# top_schematic.net
KiCad netlist of a schematic drawn in Altium Designer
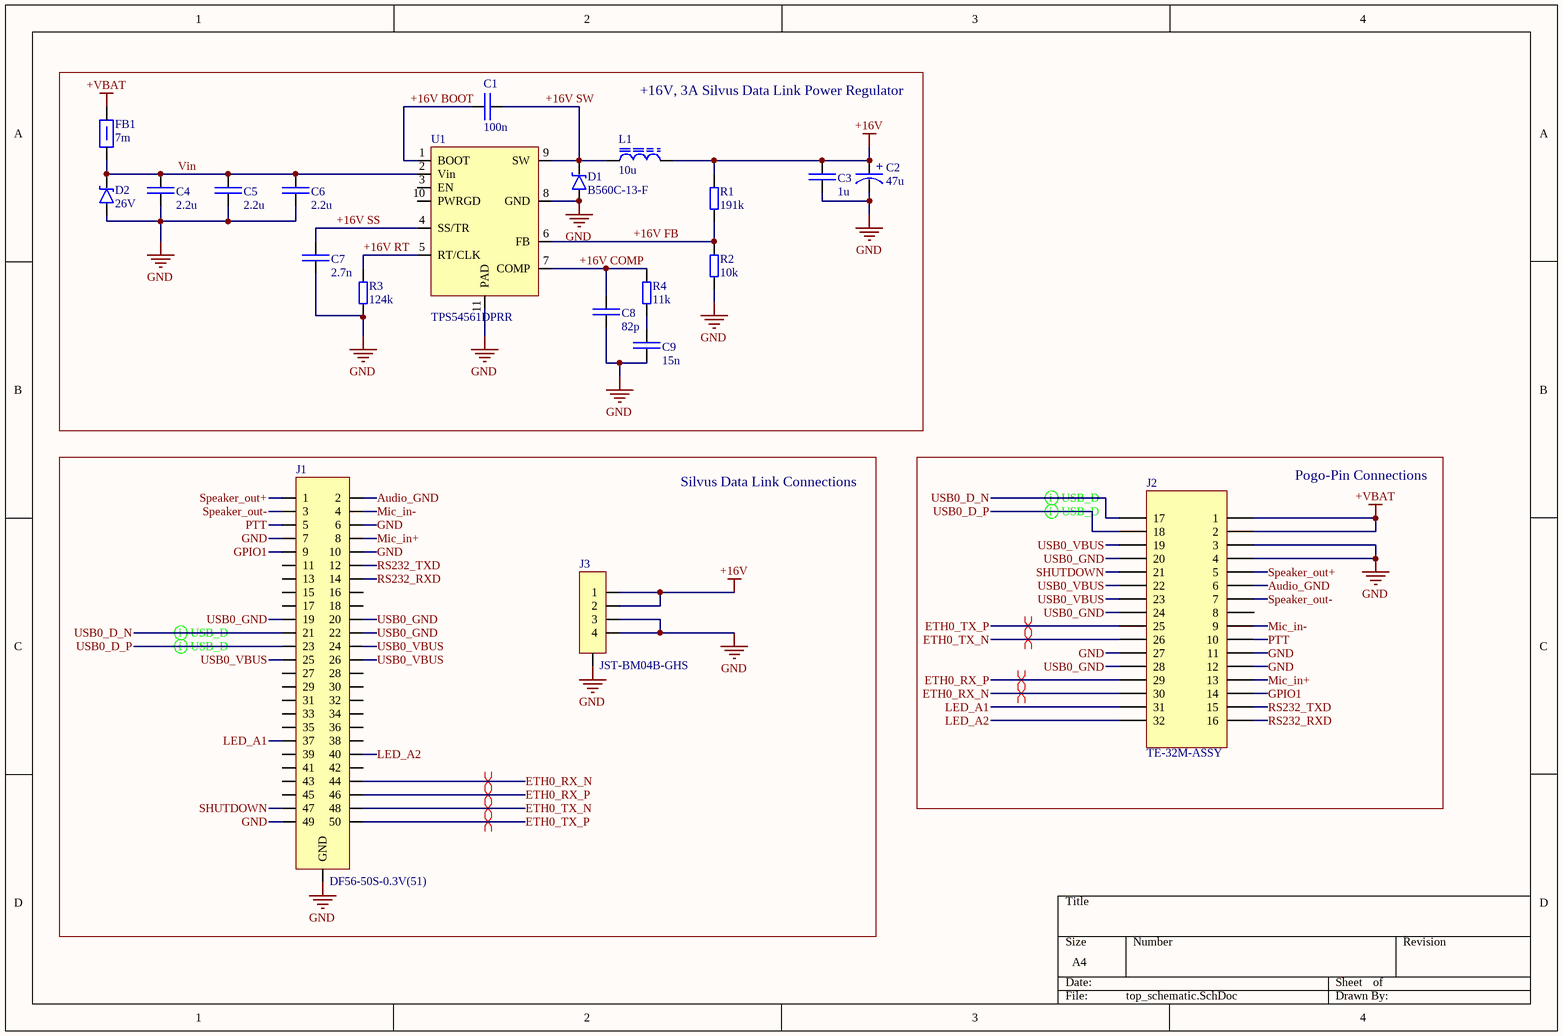
[diagram p0: top_schematic.SchDoc]

(export (version "E")
  (design (tool "Eeschema 10.0.6"))
  (components
    (comp (ref "C1")
      (value "100n")
      (footprint "CAP_0402")
      (description "0402, 100nF, 50V, X7R, ESR 0m, MLCC")
      (fields (field (name "MANUFACTURER") "Any"))
      (libsource (lib "Capacitors") (part "0402, 100nF, 50V, X7R, ESR 0m, MLCC"))
    )
    (comp (ref "C2")
      (value "47u")
      (footprint "25SVPF47M C6")
      (description "47µF 25V Aluminum Polymer Capacitor Radial, Can - SMD 30mOhm 5000 Hrs @ 105°C")
      (fields
        (field (name "MANUFACTURER") "Panasonic Electronic Components")
        (field (name "PART NUMBER") "25SVPF47M")
      )
      (libsource (lib "Capacitors") (part "47uF 25SVPF47M"))
    )
    (comp (ref "C3")
      (value "1u")
      (footprint "CAP_0805")
      (description "0805, 1uF, 50V, X7R, ESR 0m, MLCC")
      (libsource (lib "Capacitors") (part "0805, 1uF, 50V, X7R, ESR 0m, MLCC"))
    )
    (comp (ref "C4")
      (value "2.2u")
      (footprint "CAP_0805")
      (description "0805, 2.2uF, 50V, X5R, ESR 0m, MLCC")
      (fields (field (name "MANUFACTURER") "Any"))
      (libsource (lib "Capacitors") (part "0805, 2.2uF, 50V, X5R, ESR 0m, MLCC"))
    )
    (comp (ref "C5")
      (value "2.2u")
      (footprint "CAP_0805")
      (description "0805, 2.2uF, 50V, X5R, ESR 0m, MLCC")
      (fields (field (name "MANUFACTURER") "Any"))
      (libsource (lib "Capacitors") (part "0805, 2.2uF, 50V, X5R, ESR 0m, MLCC"))
    )
    (comp (ref "C6")
      (value "2.2u")
      (footprint "CAP_0805")
      (description "0805, 2.2uF, 50V, X5R, ESR 0m, MLCC")
      (fields (field (name "MANUFACTURER") "Any"))
      (libsource (lib "Capacitors") (part "0805, 2.2uF, 50V, X5R, ESR 0m, MLCC"))
    )
    (comp (ref "C7")
      (value "2.7n")
      (footprint "CAP_0402")
      (description "0402, 2.7nF, 50V, X7R, ESR 0m, MLCC")
      (fields (field (name "MANUFACTURER") "Any"))
      (libsource (lib "Capacitors") (part "0402, 2.7nF, 50V, X7R, ESR 0m, MLCC"))
    )
    (comp (ref "C8")
      (value "82p")
      (footprint "CAP_0402")
      (description "0402, 82pF, 50V, C0G/NP0, ESR 0m, MLCC")
      (fields (field (name "MANUFACTURER") "Any"))
      (libsource (lib "Capacitors") (part "0402, 82pF, 50V, C0G/NP0, ESR 0m, MLCC"))
    )
    (comp (ref "C9")
      (value "15n")
      (footprint "CAP_0402")
      (description "0402, 15nF, 50V, X7R, ESR 0m, MLCC")
      (fields (field (name "MANUFACTURER") "Any"))
      (libsource (lib "Capacitors") (part "0402, 15nF, 50V, X7R, ESR 0m, MLCC"))
    )
    (comp (ref "D1")
      (value "B560C-13-F")
      (footprint "B560C-13-F")
      (description "Diode Schottky 60V 5A Surface Mount SMC")
      (fields (field (name "MANUFACTURER") "Diodes Inc."))
      (libsource (lib "TVS_diodes") (part "B560C-13-F"))
    )
    (comp (ref "D2")
      (value "26V")
      (footprint "DO-214AC_diode")
      (description "26V Standoff, 42.1V Clamp 9.5A Ipp Tvs Diode Surface Mount DO-214AC (SMA)")
      (fields (field (name "MANUFACTURER") "Bourns") (field (name "MANUFACTURER PART NUMBER") "SMAJ26A-Q"))
      (libsource (lib "TVS_diodes") (part "SMAJ26A-Q"))
    )
    (comp (ref "FB1")
      (value "7m")
      (footprint "ferrite_0603")
      (description "23 Ohms @ 100MHz 1 Power Line Ferrite Bead 0603 (1608 Metric) 4A 7mOhm")
      (fields
        (field (name "MANUFACTURER") "Taiyo Yuden")
        (field (name "MANUFACTURER PART NUMBER") "FBMJ1608HM230NT")
      )
      (libsource (lib "Ferrites") (part "FBMJ1608HM230NT"))
    )
    (comp (ref "J1")
      (value "DF56-50S-0.3V(51)")
      (footprint "Header_Hirose_DF56")
      (description "CONN RCPT 50POS 0.012 GOLD SMD")
      (fields (field (name "MANUFACTURER") "Hirose"))
      (libsource (lib "Connectors") (part "DF56-50S-0.3V(51)"))
    )
    (comp (ref "J2")
      (value "TE-32M-ASSY")
      (footprint "TE-32M-ASSY")
      (description "API/SupplyNet pogo-pin connector, 32pins, 4 rows")
      (fields (field (name "MANUFACTURER") "SupplyNet"))
      (libsource (lib "Connectors") (part "Pogo-connector-32pin-API"))
    )
    (comp (ref "J3")
      (value "JST-BM04B-GHS")
      (footprint "JST-BM04B_HEADER")
      (description "CONN HEADER SMD 4POS 1.25MM, JST-GH series")
      (fields
        (field (name "MANUFACTURER") "JST")
        (field (name "MANUFACTURER PART NUMBER") "BM04B-GHS-TBT(LF)(SN)(N)")
      )
      (libsource (lib "Connectors") (part "BM04B-GHS-TBT(LF)(SN)(N)"))
    )
    (comp (ref "L1")
      (value "10u")
      (footprint "ETQ-P3M100HFN")
      (description "10µH Shielded  Inductor 3.7A 74.8mOhm Max 2-SMD, J-Lead")
      (fields
        (field (name "MANUFACTURER") "Panasonic Electronic Components")
        (field (name "PART NUMBER") "ETQ-P3M100HFN")
      )
      (libsource (lib "Inductors") (part "10u ETQ-P3M100HFN"))
    )
    (comp (ref "R1")
      (value "191k")
      (footprint "RES_0402")
      (description "0402, 191k, 1%, 0.1W, Res")
      (fields (field (name "MANUFACTURER") "Any"))
      (libsource (lib "Resistors") (part "Resistor 0402 191k"))
    )
    (comp (ref "R2")
      (value "10k")
      (footprint "RES_0402")
      (description "0402, 10k, 1%, 0.1W, Res")
      (fields (field (name "MANUFACTURER") "Any"))
      (libsource (lib "Resistors") (part "Resistor 0402 10k"))
    )
    (comp (ref "R3")
      (value "124k")
      (footprint "RES_0402")
      (description "0402, 124k, 1%, 0.1W, Res")
      (fields (field (name "MANUFACTURER") "Any"))
      (libsource (lib "Resistors") (part "Resistor 0402 124k"))
    )
    (comp (ref "R4")
      (value "11k")
      (footprint "RES_0402")
      (description "0402, 11k, 1%, 0.1W, Res")
      (fields (field (name "MANUFACTURER") "Any"))
      (libsource (lib "Resistors") (part "Resistor 0402 11k"))
    )
    (comp (ref "U1")
      (value "TPS54561DPRR")
      (footprint "WSON-10")
      (description "Buck, Split Rail Switching Regulator IC Positive Adjustable 0.8V 1 Output 5A 10-WDFN Exposed Pad")
      (fields (field (name "MANUFACTURER") "Texas Instruments") (field (name "PART NUMBER") "TPS54331DDA"))
      (libsource (lib "Power_IC") (part "TPS54561DPRR"))
    )
  )
  (nets
    (net (code "1") (name "+16V") (class "Default")
      (node (ref "C2") (pin "1") (pinfunction "1_1") (pintype "passive"))
      (node (ref "C3") (pin "1") (pinfunction "1_1") (pintype "passive"))
      (node (ref "J3") (pin "1") (pinfunction "1_1") (pintype "passive"))
      (node (ref "J3") (pin "2") (pinfunction "2_2") (pintype "passive"))
      (node (ref "L1") (pin "2") (pinfunction "2_2") (pintype "passive"))
      (node (ref "R1") (pin "2") (pinfunction "2_2") (pintype "passive"))
    )
    (net (code "2") (name "+VBAT") (class "Default")
      (node (ref "FB1") (pin "2") (pinfunction "2_2") (pintype "passive"))
      (node (ref "J2") (pin "1") (pinfunction "1_1") (pintype "passive"))
      (node (ref "J2") (pin "2") (pinfunction "2_2") (pintype "passive"))
    )
    (net (code "3") (name "/+16V BOOT") (class "Default")
      (node (ref "C1") (pin "2") (pinfunction "2_2") (pintype "passive"))
      (node (ref "U1") (pin "1") (pinfunction "BOOT_1") (pintype "passive"))
    )
    (net (code "4") (name "/+16V COMP") (class "Default")
      (node (ref "C8") (pin "1") (pinfunction "1_1") (pintype "passive"))
      (node (ref "R4") (pin "2") (pinfunction "2_2") (pintype "passive"))
      (node (ref "U1") (pin "7") (pinfunction "COMP_7") (pintype "passive"))
    )
    (net (code "5") (name "/+16V FB") (class "Default")
      (node (ref "R1") (pin "1") (pinfunction "1_1") (pintype "passive"))
      (node (ref "R2") (pin "2") (pinfunction "2_2") (pintype "passive"))
      (node (ref "U1") (pin "6") (pinfunction "FB_6") (pintype "passive"))
    )
    (net (code "6") (name "/+16V RT") (class "Default")
      (node (ref "R3") (pin "2") (pinfunction "2_2") (pintype "passive"))
      (node (ref "U1") (pin "5") (pinfunction "RT/CLK_5") (pintype "passive"))
    )
    (net (code "7") (name "/+16V SS") (class "Default")
      (node (ref "C7") (pin "1") (pinfunction "1_1") (pintype "passive"))
      (node (ref "U1") (pin "4") (pinfunction "SS/TR_4") (pintype "passive"))
    )
    (net (code "8") (name "/+16V SW") (class "Default")
      (node (ref "C1") (pin "1") (pinfunction "1_1") (pintype "passive"))
      (node (ref "D1") (pin "1") (pinfunction "1_1") (pintype "passive"))
      (node (ref "L1") (pin "1") (pinfunction "1_1") (pintype "passive"))
      (node (ref "U1") (pin "9") (pinfunction "SW_9") (pintype "passive"))
    )
    (net (code "9") (name "/Audio_GND") (class "Default")
      (node (ref "J1") (pin "2") (pinfunction "2_2") (pintype "passive"))
      (node (ref "J2") (pin "6") (pinfunction "6_6") (pintype "passive"))
    )
    (net (code "10") (name "/ETH0_RX_N") (class "Default")
      (node (ref "J1") (pin "44") (pinfunction "44_44") (pintype "passive"))
      (node (ref "J2") (pin "30") (pinfunction "30_30") (pintype "passive"))
    )
    (net (code "11") (name "/ETH0_RX_P") (class "Default")
      (node (ref "J1") (pin "46") (pinfunction "46_46") (pintype "passive"))
      (node (ref "J2") (pin "29") (pinfunction "29_29") (pintype "passive"))
    )
    (net (code "12") (name "/ETH0_TX_N") (class "Default")
      (node (ref "J1") (pin "48") (pinfunction "48_48") (pintype "passive"))
      (node (ref "J2") (pin "26") (pinfunction "26_26") (pintype "passive"))
    )
    (net (code "13") (name "/ETH0_TX_P") (class "Default")
      (node (ref "J1") (pin "50") (pinfunction "50_50") (pintype "passive"))
      (node (ref "J2") (pin "25") (pinfunction "25_25") (pintype "passive"))
    )
    (net (code "14") (name "/GPIO1") (class "Default")
      (node (ref "J1") (pin "9") (pinfunction "9_9") (pintype "passive"))
      (node (ref "J2") (pin "14") (pinfunction "14_14") (pintype "passive"))
    )
    (net (code "15") (name "/LED_A1") (class "Default")
      (node (ref "J1") (pin "37") (pinfunction "37_37") (pintype "passive"))
      (node (ref "J2") (pin "31") (pinfunction "31_31") (pintype "passive"))
    )
    (net (code "16") (name "/LED_A2") (class "Default")
      (node (ref "J1") (pin "40") (pinfunction "40_40") (pintype "passive"))
      (node (ref "J2") (pin "32") (pinfunction "32_32") (pintype "passive"))
    )
    (net (code "17") (name "/Mic_in+") (class "Default")
      (node (ref "J1") (pin "8") (pinfunction "8_8") (pintype "passive"))
      (node (ref "J2") (pin "13") (pinfunction "13_13") (pintype "passive"))
    )
    (net (code "18") (name "/Mic_in-") (class "Default")
      (node (ref "J1") (pin "4") (pinfunction "4_4") (pintype "passive"))
      (node (ref "J2") (pin "9") (pinfunction "9_9") (pintype "passive"))
    )
    (net (code "19") (name "/PTT") (class "Default")
      (node (ref "J1") (pin "5") (pinfunction "5_5") (pintype "passive"))
      (node (ref "J2") (pin "10") (pinfunction "10_10") (pintype "passive"))
    )
    (net (code "20") (name "/RS232_RXD") (class "Default")
      (node (ref "J1") (pin "14") (pinfunction "14_14") (pintype "passive"))
      (node (ref "J2") (pin "16") (pinfunction "16_16") (pintype "passive"))
    )
    (net (code "21") (name "/RS232_TXD") (class "Default")
      (node (ref "J1") (pin "12") (pinfunction "12_12") (pintype "passive"))
      (node (ref "J2") (pin "15") (pinfunction "15_15") (pintype "passive"))
    )
    (net (code "22") (name "/SHUTDOWN") (class "Default")
      (node (ref "J1") (pin "47") (pinfunction "47_47") (pintype "passive"))
      (node (ref "J2") (pin "21") (pinfunction "21_21") (pintype "passive"))
    )
    (net (code "23") (name "/Speaker_out+") (class "Default")
      (node (ref "J1") (pin "1") (pinfunction "1_1") (pintype "passive"))
      (node (ref "J2") (pin "5") (pinfunction "5_5") (pintype "passive"))
    )
    (net (code "24") (name "/Speaker_out-") (class "Default")
      (node (ref "J1") (pin "3") (pinfunction "3_3") (pintype "passive"))
      (node (ref "J2") (pin "7") (pinfunction "7_7") (pintype "passive"))
    )
    (net (code "25") (name "/USB0_D_N") (class "Default")
      (node (ref "J1") (pin "21") (pinfunction "21_21") (pintype "passive"))
      (node (ref "J2") (pin "17") (pinfunction "17_17") (pintype "passive"))
    )
    (net (code "26") (name "/USB0_D_P") (class "Default")
      (node (ref "J1") (pin "23") (pinfunction "23_23") (pintype "passive"))
      (node (ref "J2") (pin "18") (pinfunction "18_18") (pintype "passive"))
    )
    (net (code "27") (name "/USB0_GND") (class "Default")
      (node (ref "J1") (pin "19") (pinfunction "19_19") (pintype "passive"))
      (node (ref "J1") (pin "20") (pinfunction "20_20") (pintype "passive"))
      (node (ref "J1") (pin "22") (pinfunction "22_22") (pintype "passive"))
      (node (ref "J2") (pin "20") (pinfunction "20_20") (pintype "passive"))
      (node (ref "J2") (pin "24") (pinfunction "24_24") (pintype "passive"))
      (node (ref "J2") (pin "28") (pinfunction "28_28") (pintype "passive"))
    )
    (net (code "28") (name "/USB0_VBUS") (class "Default")
      (node (ref "J1") (pin "24") (pinfunction "24_24") (pintype "passive"))
      (node (ref "J1") (pin "25") (pinfunction "25_25") (pintype "passive"))
      (node (ref "J1") (pin "26") (pinfunction "26_26") (pintype "passive"))
      (node (ref "J2") (pin "19") (pinfunction "19_19") (pintype "passive"))
      (node (ref "J2") (pin "22") (pinfunction "22_22") (pintype "passive"))
      (node (ref "J2") (pin "23") (pinfunction "23_23") (pintype "passive"))
    )
    (net (code "29") (name "/Vin") (class "Default")
      (node (ref "C4") (pin "1") (pinfunction "1_1") (pintype "passive"))
      (node (ref "C5") (pin "1") (pinfunction "1_1") (pintype "passive"))
      (node (ref "C6") (pin "1") (pinfunction "1_1") (pintype "passive"))
      (node (ref "D2") (pin "1") (pinfunction "1_1") (pintype "passive"))
      (node (ref "FB1") (pin "1") (pinfunction "1_1") (pintype "passive"))
      (node (ref "U1") (pin "2") (pinfunction "Vin_2") (pintype "passive"))
    )
    (net (code "30") (name "GND") (class "Default")
      (node (ref "C2") (pin "2") (pinfunction "2_2") (pintype "passive"))
      (node (ref "C3") (pin "2") (pinfunction "2_2") (pintype "passive"))
      (node (ref "C4") (pin "2") (pinfunction "2_2") (pintype "passive"))
      (node (ref "C5") (pin "2") (pinfunction "2_2") (pintype "passive"))
      (node (ref "C6") (pin "2") (pinfunction "2_2") (pintype "passive"))
      (node (ref "C7") (pin "2") (pinfunction "2_2") (pintype "passive"))
      (node (ref "C8") (pin "2") (pinfunction "2_2") (pintype "passive"))
      (node (ref "C9") (pin "2") (pinfunction "2_2") (pintype "passive"))
      (node (ref "D1") (pin "2") (pinfunction "2_2") (pintype "passive"))
      (node (ref "D2") (pin "2") (pinfunction "2_2") (pintype "passive"))
      (node (ref "J1") (pin "10") (pinfunction "10_10") (pintype "passive"))
      (node (ref "J1") (pin "49") (pinfunction "49_49") (pintype "passive"))
      (node (ref "J1") (pin "6") (pinfunction "6_6") (pintype "passive"))
      (node (ref "J1") (pin "7") (pinfunction "7_7") (pintype "passive"))
      (node (ref "J1") (pin "GND") (pinfunction "GND_GND") (pintype "passive"))
      (node (ref "J2") (pin "11") (pinfunction "11_11") (pintype "passive"))
      (node (ref "J2") (pin "12") (pinfunction "12_12") (pintype "passive"))
      (node (ref "J2") (pin "27") (pinfunction "27_27") (pintype "passive"))
      (node (ref "J2") (pin "3") (pinfunction "3_3") (pintype "passive"))
      (node (ref "J2") (pin "4") (pinfunction "4_4") (pintype "passive"))
      (node (ref "J3") (pin "3") (pinfunction "3_3") (pintype "passive"))
      (node (ref "J3") (pin "4") (pinfunction "4_4") (pintype "passive"))
      (node (ref "J3") (pin "GND") (pinfunction "GND_GND") (pintype "passive"))
      (node (ref "R2") (pin "1") (pinfunction "1_1") (pintype "passive"))
      (node (ref "R3") (pin "1") (pinfunction "1_1") (pintype "passive"))
      (node (ref "U1") (pin "11") (pinfunction "PAD_11") (pintype "passive"))
      (node (ref "U1") (pin "8") (pinfunction "GND_8") (pintype "passive"))
    )
    (net (code "31") (name "Net-(C9-Pad1)") (class "Default")
      (node (ref "C9") (pin "1") (pinfunction "1_1") (pintype "passive"))
      (node (ref "R4") (pin "1") (pinfunction "1_1") (pintype "passive"))
    )
    (net (code "32") (name "unconnected-(J1-Pad11)") (class "Default")
      (node (ref "J1") (pin "11") (pinfunction "11_11") (pintype "passive"))
    )
    (net (code "33") (name "unconnected-(J1-Pad13)") (class "Default")
      (node (ref "J1") (pin "13") (pinfunction "13_13") (pintype "passive"))
    )
    (net (code "34") (name "unconnected-(J1-Pad15)") (class "Default")
      (node (ref "J1") (pin "15") (pinfunction "15_15") (pintype "passive"))
    )
    (net (code "35") (name "unconnected-(J1-Pad16)") (class "Default")
      (node (ref "J1") (pin "16") (pinfunction "16_16") (pintype "passive"))
    )
    (net (code "36") (name "unconnected-(J1-Pad17)") (class "Default")
      (node (ref "J1") (pin "17") (pinfunction "17_17") (pintype "passive"))
    )
    (net (code "37") (name "unconnected-(J1-Pad18)") (class "Default")
      (node (ref "J1") (pin "18") (pinfunction "18_18") (pintype "passive"))
    )
    (net (code "38") (name "unconnected-(J1-Pad27)") (class "Default")
      (node (ref "J1") (pin "27") (pinfunction "27_27") (pintype "passive"))
    )
    (net (code "39") (name "unconnected-(J1-Pad28)") (class "Default")
      (node (ref "J1") (pin "28") (pinfunction "28_28") (pintype "passive"))
    )
    (net (code "40") (name "unconnected-(J1-Pad29)") (class "Default")
      (node (ref "J1") (pin "29") (pinfunction "29_29") (pintype "passive"))
    )
    (net (code "41") (name "unconnected-(J1-Pad30)") (class "Default")
      (node (ref "J1") (pin "30") (pinfunction "30_30") (pintype "passive"))
    )
    (net (code "42") (name "unconnected-(J1-Pad31)") (class "Default")
      (node (ref "J1") (pin "31") (pinfunction "31_31") (pintype "passive"))
    )
    (net (code "43") (name "unconnected-(J1-Pad32)") (class "Default")
      (node (ref "J1") (pin "32") (pinfunction "32_32") (pintype "passive"))
    )
    (net (code "44") (name "unconnected-(J1-Pad33)") (class "Default")
      (node (ref "J1") (pin "33") (pinfunction "33_33") (pintype "passive"))
    )
    (net (code "45") (name "unconnected-(J1-Pad34)") (class "Default")
      (node (ref "J1") (pin "34") (pinfunction "34_34") (pintype "passive"))
    )
    (net (code "46") (name "unconnected-(J1-Pad35)") (class "Default")
      (node (ref "J1") (pin "35") (pinfunction "35_35") (pintype "passive"))
    )
    (net (code "47") (name "unconnected-(J1-Pad36)") (class "Default")
      (node (ref "J1") (pin "36") (pinfunction "36_36") (pintype "passive"))
    )
    (net (code "48") (name "unconnected-(J1-Pad38)") (class "Default")
      (node (ref "J1") (pin "38") (pinfunction "38_38") (pintype "passive"))
    )
    (net (code "49") (name "unconnected-(J1-Pad39)") (class "Default")
      (node (ref "J1") (pin "39") (pinfunction "39_39") (pintype "passive"))
    )
    (net (code "50") (name "unconnected-(J1-Pad41)") (class "Default")
      (node (ref "J1") (pin "41") (pinfunction "41_41") (pintype "passive"))
    )
    (net (code "51") (name "unconnected-(J1-Pad42)") (class "Default")
      (node (ref "J1") (pin "42") (pinfunction "42_42") (pintype "passive"))
    )
    (net (code "52") (name "unconnected-(J1-Pad43)") (class "Default")
      (node (ref "J1") (pin "43") (pinfunction "43_43") (pintype "passive"))
    )
    (net (code "53") (name "unconnected-(J1-Pad45)") (class "Default")
      (node (ref "J1") (pin "45") (pinfunction "45_45") (pintype "passive"))
    )
    (net (code "54") (name "unconnected-(J2-Pad8)") (class "Default")
      (node (ref "J2") (pin "8") (pinfunction "8_8") (pintype "passive"))
    )
    (net (code "55") (name "unconnected-(U1-EN-Pad3)") (class "Default")
      (node (ref "U1") (pin "3") (pinfunction "EN_3") (pintype "passive"))
    )
    (net (code "56") (name "unconnected-(U1-PWRGD-Pad10)") (class "Default")
      (node (ref "U1") (pin "10") (pinfunction "PWRGD_10") (pintype "passive"))
    )
  )
)
